# display.net
KiCad netlist of a schematic drawn in EAGLE
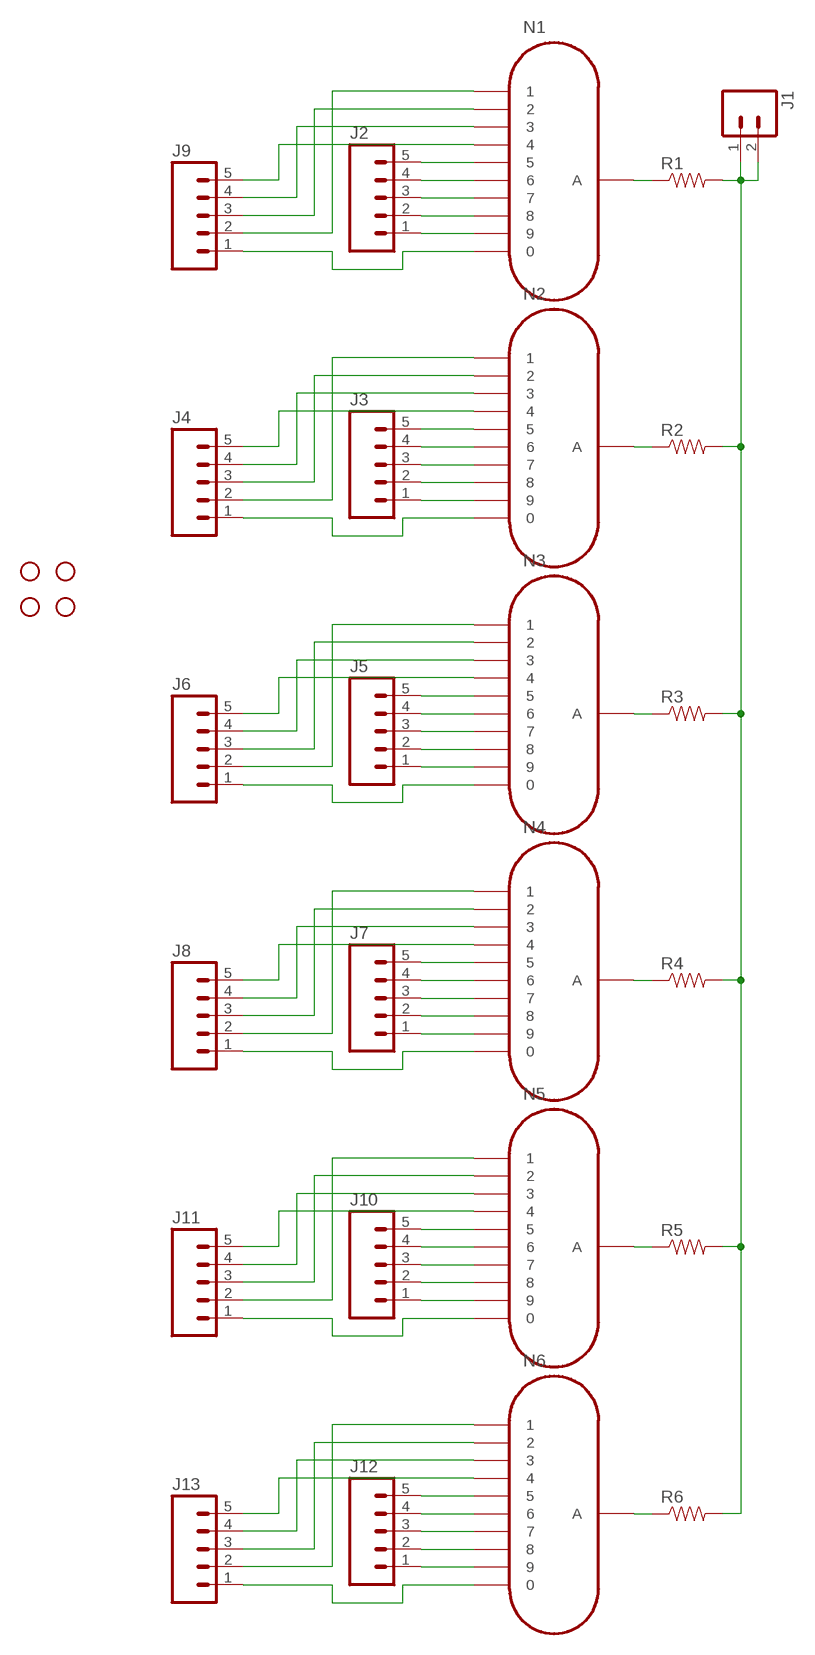
[diagram p0: schematic, sheet 1]

(export (version "E")
  (design (tool "Eeschema 10.0.6"))
  (components
    (comp (ref "H1")
      (value "STAND-OFF")
      (footprint "eagle-import:STAND-OFF")
      (libsource (lib "eagle-import") (part "STAND-OFF"))
    )
    (comp (ref "H2")
      (value "STAND-OFF")
      (footprint "eagle-import:STAND-OFF")
      (libsource (lib "eagle-import") (part "STAND-OFF"))
    )
    (comp (ref "H3")
      (value "STAND-OFF")
      (footprint "eagle-import:STAND-OFF")
      (libsource (lib "eagle-import") (part "STAND-OFF"))
    )
    (comp (ref "H4")
      (value "STAND-OFF")
      (footprint "eagle-import:STAND-OFF")
      (libsource (lib "eagle-import") (part "STAND-OFF"))
    )
    (comp (ref "J1")
      (value "M02PTH")
      (footprint "eagle-import:1X02")
      (libsource (lib "eagle-import") (part "M02PTH"))
    )
    (comp (ref "J2")
      (value "M05PTH")
      (footprint "eagle-import:1X05")
      (libsource (lib "eagle-import") (part "M05PTH"))
    )
    (comp (ref "J3")
      (value "M05PTH")
      (footprint "eagle-import:1X05")
      (libsource (lib "eagle-import") (part "M05PTH"))
    )
    (comp (ref "J4")
      (value "M05PTH")
      (footprint "eagle-import:1X05")
      (libsource (lib "eagle-import") (part "M05PTH"))
    )
    (comp (ref "J5")
      (value "M05PTH")
      (footprint "eagle-import:1X05")
      (libsource (lib "eagle-import") (part "M05PTH"))
    )
    (comp (ref "J6")
      (value "M05PTH")
      (footprint "eagle-import:1X05")
      (libsource (lib "eagle-import") (part "M05PTH"))
    )
    (comp (ref "J7")
      (value "M05PTH")
      (footprint "eagle-import:1X05")
      (libsource (lib "eagle-import") (part "M05PTH"))
    )
    (comp (ref "J8")
      (value "M05PTH")
      (footprint "eagle-import:1X05")
      (libsource (lib "eagle-import") (part "M05PTH"))
    )
    (comp (ref "J9")
      (value "M05PTH")
      (footprint "eagle-import:1X05")
      (libsource (lib "eagle-import") (part "M05PTH"))
    )
    (comp (ref "J10")
      (value "M05PTH")
      (footprint "eagle-import:1X05")
      (libsource (lib "eagle-import") (part "M05PTH"))
    )
    (comp (ref "J11")
      (value "M05PTH")
      (footprint "eagle-import:1X05")
      (libsource (lib "eagle-import") (part "M05PTH"))
    )
    (comp (ref "J12")
      (value "M05PTH")
      (footprint "eagle-import:1X05")
      (libsource (lib "eagle-import") (part "M05PTH"))
    )
    (comp (ref "J13")
      (value "M05PTH")
      (footprint "eagle-import:1X05")
      (libsource (lib "eagle-import") (part "M05PTH"))
    )
    (comp (ref "N1")
      (value "IN-12A")
      (footprint "eagle-import:IN-12")
      (libsource (lib "eagle-import") (part "IN-12A"))
    )
    (comp (ref "N2")
      (value "IN-12A")
      (footprint "eagle-import:IN-12")
      (libsource (lib "eagle-import") (part "IN-12A"))
    )
    (comp (ref "N3")
      (value "IN-12A")
      (footprint "eagle-import:IN-12")
      (libsource (lib "eagle-import") (part "IN-12A"))
    )
    (comp (ref "N4")
      (value "IN-12A")
      (footprint "eagle-import:IN-12")
      (libsource (lib "eagle-import") (part "IN-12A"))
    )
    (comp (ref "N5")
      (value "IN-12A")
      (footprint "eagle-import:IN-12")
      (libsource (lib "eagle-import") (part "IN-12A"))
    )
    (comp (ref "N6")
      (value "IN-12A")
      (footprint "eagle-import:IN-12")
      (libsource (lib "eagle-import") (part "IN-12A"))
    )
    (comp (ref "R1")
      (value "RESISTOR0805-RES")
      (footprint "eagle-import:0805")
      (libsource (lib "eagle-import") (part "RESISTOR0805-RES"))
    )
    (comp (ref "R2")
      (value "RESISTOR0805-RES")
      (footprint "eagle-import:0805")
      (libsource (lib "eagle-import") (part "RESISTOR0805-RES"))
    )
    (comp (ref "R3")
      (value "RESISTOR0805-RES")
      (footprint "eagle-import:0805")
      (libsource (lib "eagle-import") (part "RESISTOR0805-RES"))
    )
    (comp (ref "R4")
      (value "RESISTOR0805-RES")
      (footprint "eagle-import:0805")
      (libsource (lib "eagle-import") (part "RESISTOR0805-RES"))
    )
    (comp (ref "R5")
      (value "RESISTOR0805-RES")
      (footprint "eagle-import:0805")
      (libsource (lib "eagle-import") (part "RESISTOR0805-RES"))
    )
    (comp (ref "R6")
      (value "RESISTOR0805-RES")
      (footprint "eagle-import:0805")
      (libsource (lib "eagle-import") (part "RESISTOR0805-RES"))
    )
  )
  (nets
    (net (code "1") (name "Net-(J1-Pad1)") (class "Default")
      (node (ref "J1") (pin "1") (pinfunction "1_1") (pintype "passive"))
      (node (ref "J1") (pin "2") (pinfunction "2_2") (pintype "passive"))
      (node (ref "R1") (pin "2") (pinfunction "2_2") (pintype "passive"))
      (node (ref "R2") (pin "2") (pinfunction "2_2") (pintype "passive"))
      (node (ref "R3") (pin "2") (pinfunction "2_2") (pintype "passive"))
      (node (ref "R4") (pin "2") (pinfunction "2_2") (pintype "passive"))
      (node (ref "R5") (pin "2") (pinfunction "2_2") (pintype "passive"))
      (node (ref "R6") (pin "2") (pinfunction "2_2") (pintype "passive"))
    )
    (net (code "2") (name "Net-(J2-Pad1)") (class "Default")
      (node (ref "J2") (pin "1") (pinfunction "1_1") (pintype "passive"))
      (node (ref "N1") (pin "9") (pinfunction "9_9") (pintype "bidirectional"))
    )
    (net (code "3") (name "Net-(J2-Pad2)") (class "Default")
      (node (ref "J2") (pin "2") (pinfunction "2_2") (pintype "passive"))
      (node (ref "N1") (pin "8") (pinfunction "8_8") (pintype "bidirectional"))
    )
    (net (code "4") (name "Net-(J2-Pad3)") (class "Default")
      (node (ref "J2") (pin "3") (pinfunction "3_3") (pintype "passive"))
      (node (ref "N1") (pin "7") (pinfunction "7_7") (pintype "bidirectional"))
    )
    (net (code "5") (name "Net-(J2-Pad4)") (class "Default")
      (node (ref "J2") (pin "4") (pinfunction "4_4") (pintype "passive"))
      (node (ref "N1") (pin "6") (pinfunction "6_6") (pintype "bidirectional"))
    )
    (net (code "6") (name "Net-(J2-Pad5)") (class "Default")
      (node (ref "J2") (pin "5") (pinfunction "5_5") (pintype "passive"))
      (node (ref "N1") (pin "5") (pinfunction "5_5") (pintype "bidirectional"))
    )
    (net (code "7") (name "Net-(J3-Pad1)") (class "Default")
      (node (ref "J3") (pin "1") (pinfunction "1_1") (pintype "passive"))
      (node (ref "N2") (pin "9") (pinfunction "9_9") (pintype "bidirectional"))
    )
    (net (code "8") (name "Net-(J3-Pad2)") (class "Default")
      (node (ref "J3") (pin "2") (pinfunction "2_2") (pintype "passive"))
      (node (ref "N2") (pin "8") (pinfunction "8_8") (pintype "bidirectional"))
    )
    (net (code "9") (name "Net-(J3-Pad3)") (class "Default")
      (node (ref "J3") (pin "3") (pinfunction "3_3") (pintype "passive"))
      (node (ref "N2") (pin "7") (pinfunction "7_7") (pintype "bidirectional"))
    )
    (net (code "10") (name "Net-(J3-Pad4)") (class "Default")
      (node (ref "J3") (pin "4") (pinfunction "4_4") (pintype "passive"))
      (node (ref "N2") (pin "6") (pinfunction "6_6") (pintype "bidirectional"))
    )
    (net (code "11") (name "Net-(J3-Pad5)") (class "Default")
      (node (ref "J3") (pin "5") (pinfunction "5_5") (pintype "passive"))
      (node (ref "N2") (pin "5") (pinfunction "5_5") (pintype "bidirectional"))
    )
    (net (code "12") (name "Net-(J4-Pad1)") (class "Default")
      (node (ref "J4") (pin "1") (pinfunction "1_1") (pintype "passive"))
      (node (ref "N2") (pin "0") (pinfunction "0_0") (pintype "bidirectional"))
    )
    (net (code "13") (name "Net-(J4-Pad2)") (class "Default")
      (node (ref "J4") (pin "2") (pinfunction "2_2") (pintype "passive"))
      (node (ref "N2") (pin "1") (pinfunction "1_1") (pintype "bidirectional"))
    )
    (net (code "14") (name "Net-(J4-Pad3)") (class "Default")
      (node (ref "J4") (pin "3") (pinfunction "3_3") (pintype "passive"))
      (node (ref "N2") (pin "2") (pinfunction "2_2") (pintype "bidirectional"))
    )
    (net (code "15") (name "Net-(J4-Pad4)") (class "Default")
      (node (ref "J4") (pin "4") (pinfunction "4_4") (pintype "passive"))
      (node (ref "N2") (pin "3") (pinfunction "3_3") (pintype "bidirectional"))
    )
    (net (code "16") (name "Net-(J4-Pad5)") (class "Default")
      (node (ref "J4") (pin "5") (pinfunction "5_5") (pintype "passive"))
      (node (ref "N2") (pin "4") (pinfunction "4_4") (pintype "bidirectional"))
    )
    (net (code "17") (name "Net-(J5-Pad1)") (class "Default")
      (node (ref "J5") (pin "1") (pinfunction "1_1") (pintype "passive"))
      (node (ref "N3") (pin "9") (pinfunction "9_9") (pintype "bidirectional"))
    )
    (net (code "18") (name "Net-(J5-Pad2)") (class "Default")
      (node (ref "J5") (pin "2") (pinfunction "2_2") (pintype "passive"))
      (node (ref "N3") (pin "8") (pinfunction "8_8") (pintype "bidirectional"))
    )
    (net (code "19") (name "Net-(J5-Pad3)") (class "Default")
      (node (ref "J5") (pin "3") (pinfunction "3_3") (pintype "passive"))
      (node (ref "N3") (pin "7") (pinfunction "7_7") (pintype "bidirectional"))
    )
    (net (code "20") (name "Net-(J5-Pad4)") (class "Default")
      (node (ref "J5") (pin "4") (pinfunction "4_4") (pintype "passive"))
      (node (ref "N3") (pin "6") (pinfunction "6_6") (pintype "bidirectional"))
    )
    (net (code "21") (name "Net-(J5-Pad5)") (class "Default")
      (node (ref "J5") (pin "5") (pinfunction "5_5") (pintype "passive"))
      (node (ref "N3") (pin "5") (pinfunction "5_5") (pintype "bidirectional"))
    )
    (net (code "22") (name "Net-(J6-Pad1)") (class "Default")
      (node (ref "J6") (pin "1") (pinfunction "1_1") (pintype "passive"))
      (node (ref "N3") (pin "0") (pinfunction "0_0") (pintype "bidirectional"))
    )
    (net (code "23") (name "Net-(J6-Pad2)") (class "Default")
      (node (ref "J6") (pin "2") (pinfunction "2_2") (pintype "passive"))
      (node (ref "N3") (pin "1") (pinfunction "1_1") (pintype "bidirectional"))
    )
    (net (code "24") (name "Net-(J6-Pad3)") (class "Default")
      (node (ref "J6") (pin "3") (pinfunction "3_3") (pintype "passive"))
      (node (ref "N3") (pin "2") (pinfunction "2_2") (pintype "bidirectional"))
    )
    (net (code "25") (name "Net-(J6-Pad4)") (class "Default")
      (node (ref "J6") (pin "4") (pinfunction "4_4") (pintype "passive"))
      (node (ref "N3") (pin "3") (pinfunction "3_3") (pintype "bidirectional"))
    )
    (net (code "26") (name "Net-(J6-Pad5)") (class "Default")
      (node (ref "J6") (pin "5") (pinfunction "5_5") (pintype "passive"))
      (node (ref "N3") (pin "4") (pinfunction "4_4") (pintype "bidirectional"))
    )
    (net (code "27") (name "Net-(J7-Pad1)") (class "Default")
      (node (ref "J7") (pin "1") (pinfunction "1_1") (pintype "passive"))
      (node (ref "N4") (pin "9") (pinfunction "9_9") (pintype "bidirectional"))
    )
    (net (code "28") (name "Net-(J7-Pad2)") (class "Default")
      (node (ref "J7") (pin "2") (pinfunction "2_2") (pintype "passive"))
      (node (ref "N4") (pin "8") (pinfunction "8_8") (pintype "bidirectional"))
    )
    (net (code "29") (name "Net-(J7-Pad3)") (class "Default")
      (node (ref "J7") (pin "3") (pinfunction "3_3") (pintype "passive"))
      (node (ref "N4") (pin "7") (pinfunction "7_7") (pintype "bidirectional"))
    )
    (net (code "30") (name "Net-(J7-Pad4)") (class "Default")
      (node (ref "J7") (pin "4") (pinfunction "4_4") (pintype "passive"))
      (node (ref "N4") (pin "6") (pinfunction "6_6") (pintype "bidirectional"))
    )
    (net (code "31") (name "Net-(J7-Pad5)") (class "Default")
      (node (ref "J7") (pin "5") (pinfunction "5_5") (pintype "passive"))
      (node (ref "N4") (pin "5") (pinfunction "5_5") (pintype "bidirectional"))
    )
    (net (code "32") (name "Net-(J8-Pad1)") (class "Default")
      (node (ref "J8") (pin "1") (pinfunction "1_1") (pintype "passive"))
      (node (ref "N4") (pin "0") (pinfunction "0_0") (pintype "bidirectional"))
    )
    (net (code "33") (name "Net-(J8-Pad2)") (class "Default")
      (node (ref "J8") (pin "2") (pinfunction "2_2") (pintype "passive"))
      (node (ref "N4") (pin "1") (pinfunction "1_1") (pintype "bidirectional"))
    )
    (net (code "34") (name "Net-(J8-Pad3)") (class "Default")
      (node (ref "J8") (pin "3") (pinfunction "3_3") (pintype "passive"))
      (node (ref "N4") (pin "2") (pinfunction "2_2") (pintype "bidirectional"))
    )
    (net (code "35") (name "Net-(J8-Pad4)") (class "Default")
      (node (ref "J8") (pin "4") (pinfunction "4_4") (pintype "passive"))
      (node (ref "N4") (pin "3") (pinfunction "3_3") (pintype "bidirectional"))
    )
    (net (code "36") (name "Net-(J8-Pad5)") (class "Default")
      (node (ref "J8") (pin "5") (pinfunction "5_5") (pintype "passive"))
      (node (ref "N4") (pin "4") (pinfunction "4_4") (pintype "bidirectional"))
    )
    (net (code "37") (name "Net-(J9-Pad1)") (class "Default")
      (node (ref "J9") (pin "1") (pinfunction "1_1") (pintype "passive"))
      (node (ref "N1") (pin "0") (pinfunction "0_0") (pintype "bidirectional"))
    )
    (net (code "38") (name "Net-(J9-Pad2)") (class "Default")
      (node (ref "J9") (pin "2") (pinfunction "2_2") (pintype "passive"))
      (node (ref "N1") (pin "1") (pinfunction "1_1") (pintype "bidirectional"))
    )
    (net (code "39") (name "Net-(J9-Pad3)") (class "Default")
      (node (ref "J9") (pin "3") (pinfunction "3_3") (pintype "passive"))
      (node (ref "N1") (pin "2") (pinfunction "2_2") (pintype "bidirectional"))
    )
    (net (code "40") (name "Net-(J9-Pad4)") (class "Default")
      (node (ref "J9") (pin "4") (pinfunction "4_4") (pintype "passive"))
      (node (ref "N1") (pin "3") (pinfunction "3_3") (pintype "bidirectional"))
    )
    (net (code "41") (name "Net-(J9-Pad5)") (class "Default")
      (node (ref "J9") (pin "5") (pinfunction "5_5") (pintype "passive"))
      (node (ref "N1") (pin "4") (pinfunction "4_4") (pintype "bidirectional"))
    )
    (net (code "42") (name "Net-(J10-Pad1)") (class "Default")
      (node (ref "J10") (pin "1") (pinfunction "1_1") (pintype "passive"))
      (node (ref "N5") (pin "9") (pinfunction "9_9") (pintype "bidirectional"))
    )
    (net (code "43") (name "Net-(J10-Pad2)") (class "Default")
      (node (ref "J10") (pin "2") (pinfunction "2_2") (pintype "passive"))
      (node (ref "N5") (pin "8") (pinfunction "8_8") (pintype "bidirectional"))
    )
    (net (code "44") (name "Net-(J10-Pad3)") (class "Default")
      (node (ref "J10") (pin "3") (pinfunction "3_3") (pintype "passive"))
      (node (ref "N5") (pin "7") (pinfunction "7_7") (pintype "bidirectional"))
    )
    (net (code "45") (name "Net-(J10-Pad4)") (class "Default")
      (node (ref "J10") (pin "4") (pinfunction "4_4") (pintype "passive"))
      (node (ref "N5") (pin "6") (pinfunction "6_6") (pintype "bidirectional"))
    )
    (net (code "46") (name "Net-(J10-Pad5)") (class "Default")
      (node (ref "J10") (pin "5") (pinfunction "5_5") (pintype "passive"))
      (node (ref "N5") (pin "5") (pinfunction "5_5") (pintype "bidirectional"))
    )
    (net (code "47") (name "Net-(J11-Pad1)") (class "Default")
      (node (ref "J11") (pin "1") (pinfunction "1_1") (pintype "passive"))
      (node (ref "N5") (pin "0") (pinfunction "0_0") (pintype "bidirectional"))
    )
    (net (code "48") (name "Net-(J11-Pad2)") (class "Default")
      (node (ref "J11") (pin "2") (pinfunction "2_2") (pintype "passive"))
      (node (ref "N5") (pin "1") (pinfunction "1_1") (pintype "bidirectional"))
    )
    (net (code "49") (name "Net-(J11-Pad3)") (class "Default")
      (node (ref "J11") (pin "3") (pinfunction "3_3") (pintype "passive"))
      (node (ref "N5") (pin "2") (pinfunction "2_2") (pintype "bidirectional"))
    )
    (net (code "50") (name "Net-(J11-Pad4)") (class "Default")
      (node (ref "J11") (pin "4") (pinfunction "4_4") (pintype "passive"))
      (node (ref "N5") (pin "3") (pinfunction "3_3") (pintype "bidirectional"))
    )
    (net (code "51") (name "Net-(J11-Pad5)") (class "Default")
      (node (ref "J11") (pin "5") (pinfunction "5_5") (pintype "passive"))
      (node (ref "N5") (pin "4") (pinfunction "4_4") (pintype "bidirectional"))
    )
    (net (code "52") (name "Net-(J12-Pad1)") (class "Default")
      (node (ref "J12") (pin "1") (pinfunction "1_1") (pintype "passive"))
      (node (ref "N6") (pin "9") (pinfunction "9_9") (pintype "bidirectional"))
    )
    (net (code "53") (name "Net-(J12-Pad2)") (class "Default")
      (node (ref "J12") (pin "2") (pinfunction "2_2") (pintype "passive"))
      (node (ref "N6") (pin "8") (pinfunction "8_8") (pintype "bidirectional"))
    )
    (net (code "54") (name "Net-(J12-Pad3)") (class "Default")
      (node (ref "J12") (pin "3") (pinfunction "3_3") (pintype "passive"))
      (node (ref "N6") (pin "7") (pinfunction "7_7") (pintype "bidirectional"))
    )
    (net (code "55") (name "Net-(J12-Pad4)") (class "Default")
      (node (ref "J12") (pin "4") (pinfunction "4_4") (pintype "passive"))
      (node (ref "N6") (pin "6") (pinfunction "6_6") (pintype "bidirectional"))
    )
    (net (code "56") (name "Net-(J12-Pad5)") (class "Default")
      (node (ref "J12") (pin "5") (pinfunction "5_5") (pintype "passive"))
      (node (ref "N6") (pin "5") (pinfunction "5_5") (pintype "bidirectional"))
    )
    (net (code "57") (name "Net-(J13-Pad1)") (class "Default")
      (node (ref "J13") (pin "1") (pinfunction "1_1") (pintype "passive"))
      (node (ref "N6") (pin "0") (pinfunction "0_0") (pintype "bidirectional"))
    )
    (net (code "58") (name "Net-(J13-Pad2)") (class "Default")
      (node (ref "J13") (pin "2") (pinfunction "2_2") (pintype "passive"))
      (node (ref "N6") (pin "1") (pinfunction "1_1") (pintype "bidirectional"))
    )
    (net (code "59") (name "Net-(J13-Pad3)") (class "Default")
      (node (ref "J13") (pin "3") (pinfunction "3_3") (pintype "passive"))
      (node (ref "N6") (pin "2") (pinfunction "2_2") (pintype "bidirectional"))
    )
    (net (code "60") (name "Net-(J13-Pad4)") (class "Default")
      (node (ref "J13") (pin "4") (pinfunction "4_4") (pintype "passive"))
      (node (ref "N6") (pin "3") (pinfunction "3_3") (pintype "bidirectional"))
    )
    (net (code "61") (name "Net-(J13-Pad5)") (class "Default")
      (node (ref "J13") (pin "5") (pinfunction "5_5") (pintype "passive"))
      (node (ref "N6") (pin "4") (pinfunction "4_4") (pintype "bidirectional"))
    )
    (net (code "62") (name "Net-(N1-PadA)") (class "Default")
      (node (ref "N1") (pin "A") (pinfunction "A_A") (pintype "bidirectional"))
      (node (ref "R1") (pin "1") (pinfunction "1_1") (pintype "passive"))
    )
    (net (code "63") (name "Net-(N2-PadA)") (class "Default")
      (node (ref "N2") (pin "A") (pinfunction "A_A") (pintype "bidirectional"))
      (node (ref "R2") (pin "1") (pinfunction "1_1") (pintype "passive"))
    )
    (net (code "64") (name "Net-(N3-PadA)") (class "Default")
      (node (ref "N3") (pin "A") (pinfunction "A_A") (pintype "bidirectional"))
      (node (ref "R3") (pin "1") (pinfunction "1_1") (pintype "passive"))
    )
    (net (code "65") (name "Net-(N4-PadA)") (class "Default")
      (node (ref "N4") (pin "A") (pinfunction "A_A") (pintype "bidirectional"))
      (node (ref "R4") (pin "1") (pinfunction "1_1") (pintype "passive"))
    )
    (net (code "66") (name "Net-(N5-PadA)") (class "Default")
      (node (ref "N5") (pin "A") (pinfunction "A_A") (pintype "bidirectional"))
      (node (ref "R5") (pin "1") (pinfunction "1_1") (pintype "passive"))
    )
    (net (code "67") (name "Net-(N6-PadA)") (class "Default")
      (node (ref "N6") (pin "A") (pinfunction "A_A") (pintype "bidirectional"))
      (node (ref "R6") (pin "1") (pinfunction "1_1") (pintype "passive"))
    )
  )
)
